# EVGP_Estop_Daugherboard.net
KiCad netlist of a schematic drawn in EAGLE
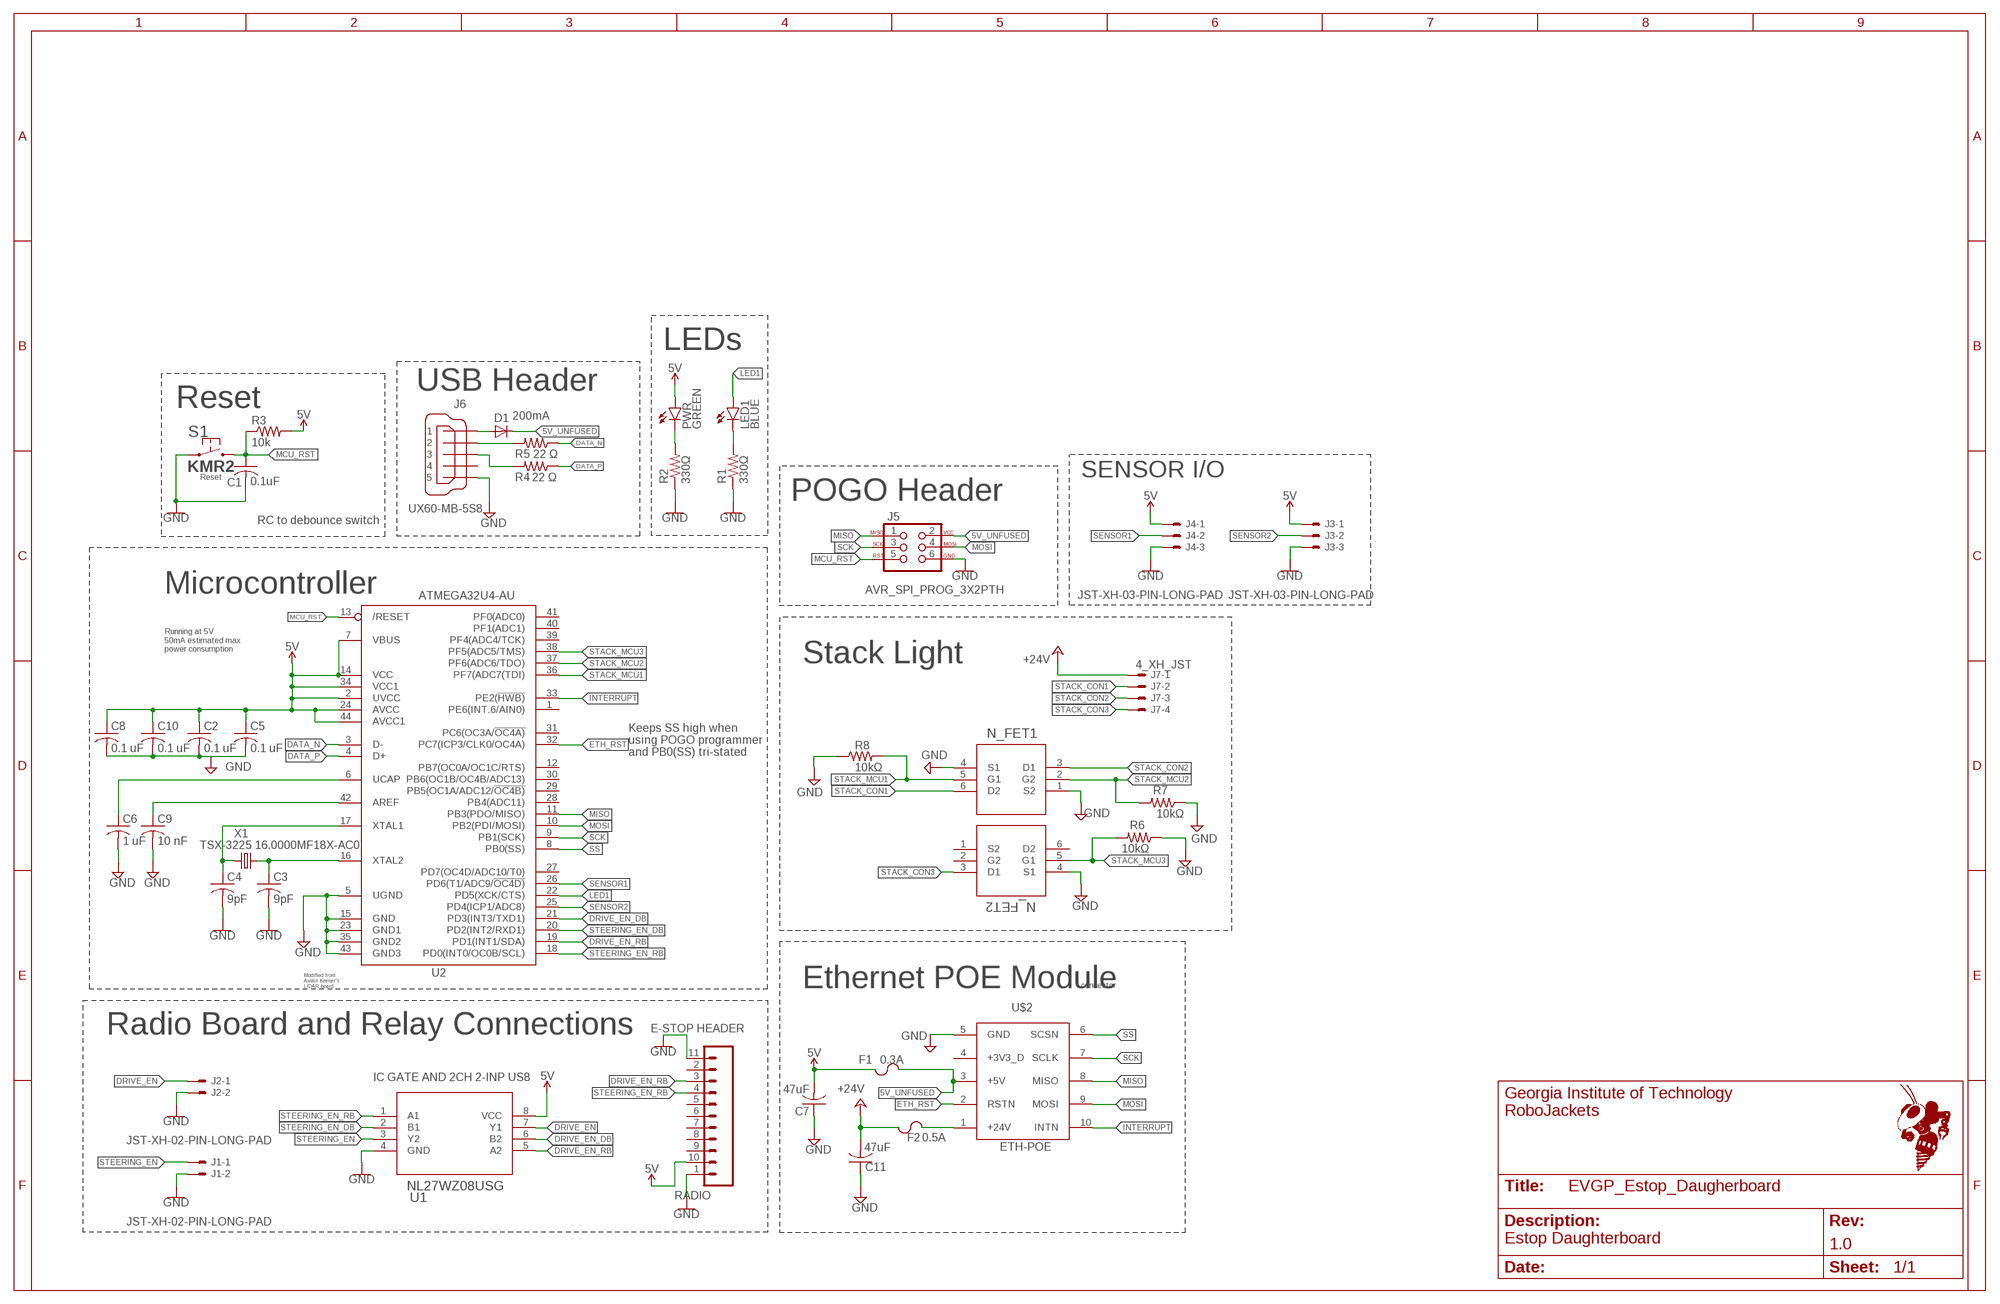
[diagram p0: schematic, sheet 1]

(export (version "E")
  (design (tool "Eeschema 10.0.6"))
  (components
    (comp (ref "C1")
      (value "0.1uF")
      (footprint "eagle-import:C0603")
      (libsource (lib "eagle-import") (part "C-USC0603"))
    )
    (comp (ref "C2")
      (value "0.1 uF")
      (footprint "eagle-import:C0603")
      (libsource (lib "eagle-import") (part "resistor_348_C-USC0603"))
    )
    (comp (ref "C3")
      (value "9pF")
      (footprint "eagle-import:C0603")
      (libsource (lib "eagle-import") (part "resistor_348_C-USC0603"))
    )
    (comp (ref "C4")
      (value "9pF")
      (footprint "eagle-import:C0603")
      (libsource (lib "eagle-import") (part "resistor_348_C-USC0603"))
    )
    (comp (ref "C5")
      (value "0.1 uF")
      (footprint "eagle-import:C0603")
      (libsource (lib "eagle-import") (part "resistor_348_C-USC0603"))
    )
    (comp (ref "C6")
      (value "1 uF")
      (footprint "eagle-import:C0603")
      (libsource (lib "eagle-import") (part "resistor_348_C-USC0603"))
    )
    (comp (ref "C7")
      (value "47uF")
      (footprint "eagle-import:C1206")
      (libsource (lib "eagle-import") (part "C-USC1206"))
    )
    (comp (ref "C8")
      (value "0.1 uF")
      (footprint "eagle-import:C0603")
      (libsource (lib "eagle-import") (part "resistor_348_C-USC0603"))
    )
    (comp (ref "C9")
      (value "10 nF")
      (footprint "eagle-import:C0603")
      (libsource (lib "eagle-import") (part "resistor_348_C-USC0603"))
    )
    (comp (ref "C10")
      (value "0.1 uF")
      (footprint "eagle-import:C0603")
      (libsource (lib "eagle-import") (part "resistor_348_C-USC0603"))
    )
    (comp (ref "C11")
      (value "47uF")
      (footprint "eagle-import:C1206")
      (libsource (lib "eagle-import") (part "C-USC1206"))
    )
    (comp (ref "D1")
      (value "200mA")
      (footprint "eagle-import:SOD323-R")
      (libsource (lib "eagle-import") (part "DIODE-SOD323-R"))
    )
    (comp (ref "F1")
      (value "0.3A")
      (footprint "eagle-import:F1206")
      (libsource (lib "eagle-import") (part "CHIP_FUSE1206"))
    )
    (comp (ref "F2")
      (value "0.5A")
      (footprint "eagle-import:F1206")
      (libsource (lib "eagle-import") (part "CHIP_FUSE1206"))
    )
    (comp (ref "J1")
      (value "JST-XH-02-PIN-LONG-PAD")
      (footprint "eagle-import:JST-XH-02-PACKAGE-LONG-PAD")
      (libsource (lib "eagle-import") (part "JST-XH-02-PIN-LONG-PAD"))
    )
    (comp (ref "J2")
      (value "JST-XH-02-PIN-LONG-PAD")
      (footprint "eagle-import:JST-XH-02-PACKAGE-LONG-PAD")
      (libsource (lib "eagle-import") (part "JST-XH-02-PIN-LONG-PAD"))
    )
    (comp (ref "J3")
      (value "JST-XH-03-PIN-LONG-PAD")
      (footprint "eagle-import:JST-XH-03-PACKAGE-LONG-PAD")
      (libsource (lib "eagle-import") (part "JST-XH-03-PIN-LONG-PAD"))
    )
    (comp (ref "J4")
      (value "JST-XH-03-PIN-LONG-PAD")
      (footprint "eagle-import:JST-XH-03-PACKAGE-LONG-PAD")
      (libsource (lib "eagle-import") (part "JST-XH-03-PIN-LONG-PAD"))
    )
    (comp (ref "J5")
      (value "AVR_SPI_PROG_3X2PTH")
      (footprint "eagle-import:2X3")
      (libsource (lib "eagle-import") (part "AVR_SPI_PROG_3X2PTH"))
    )
    (comp (ref "J6")
      (value "UX60-MB-5S8")
      (footprint "eagle-import:UX60-MB-5S8")
      (libsource (lib "eagle-import") (part "UX60-MB-5S?8"))
    )
    (comp (ref "J7")
      (value "4_XH_JST")
      (footprint "eagle-import:JST-XH-04-PACKAGE-LONG-PAD")
      (libsource (lib "eagle-import") (part "JST-XH-04-PIN-LONG-PAD"))
    )
    (comp (ref "LED1")
      (value "BLUE")
      (footprint "eagle-import:CHIP-LED0603")
      (libsource (lib "eagle-import") (part "LEDCHIP-LED0603"))
    )
    (comp (ref "PWR")
      (value "GREEN")
      (footprint "eagle-import:CHIP-LED0603")
      (libsource (lib "eagle-import") (part "LEDCHIP-LED0603"))
    )
    (comp (ref "Q1")
      (value "N_FET2")
      (footprint "eagle-import:SOT-363")
      (fields (field (name "MANUFACTURER_PART_NUMBER") "BSS84DW7F"))
      (libsource (lib "eagle-import") (part "BSS84DW-7-F"))
    )
    (comp (ref "Q2")
      (value "N_FET1")
      (footprint "eagle-import:SOT-363")
      (fields (field (name "MANUFACTURER_PART_NUMBER") "BSS84DW7F"))
      (libsource (lib "eagle-import") (part "BSS84DW-7-F"))
    )
    (comp (ref "R1")
      (value "330Ω")
      (footprint "eagle-import:R0603")
      (libsource (lib "eagle-import") (part "R-US_R0603"))
    )
    (comp (ref "R2")
      (value "330Ω")
      (footprint "eagle-import:R0603")
      (libsource (lib "eagle-import") (part "R-US_R0603"))
    )
    (comp (ref "R3")
      (value "10k")
      (footprint "eagle-import:R0603")
      (libsource (lib "eagle-import") (part "R-US_R0603"))
    )
    (comp (ref "R4")
      (value "22 Ω")
      (footprint "eagle-import:R0603")
      (libsource (lib "eagle-import") (part "R-US_R0603"))
    )
    (comp (ref "R5")
      (value "22 Ω")
      (footprint "eagle-import:R0603")
      (libsource (lib "eagle-import") (part "R-US_R0603"))
    )
    (comp (ref "R6")
      (value "10kΩ")
      (footprint "eagle-import:R0603")
      (libsource (lib "eagle-import") (part "R-US_R0603"))
    )
    (comp (ref "R7")
      (value "10kΩ")
      (footprint "eagle-import:R0603")
      (libsource (lib "eagle-import") (part "R-US_R0603"))
    )
    (comp (ref "R8")
      (value "10kΩ")
      (footprint "eagle-import:R0603")
      (libsource (lib "eagle-import") (part "R-US_R0603"))
    )
    (comp (ref "RADIO")
      (value "E-STOP HEADER")
      (footprint "eagle-import:RADIO_V1.3")
      (libsource (lib "eagle-import") (part "ESTOP_RADIO"))
    )
    (comp (ref "S1")
      (value "KMR2")
      (footprint "eagle-import:KMR2")
      (fields (field (name "FUNCTION") "Reset"))
      (libsource (lib "eagle-import") (part "KMR2"))
    )
    (comp (ref "U$2")
      (value "ETH-POE")
      (footprint "eagle-import:HDRVR10W64P4000X254_2X5_1016X508X254B")
      (libsource (lib "eagle-import") (part "ETH-POE"))
    )
    (comp (ref "U1")
      (value "NL27WZ08USG")
      (footprint "eagle-import:US8_2P40X2P10")
      (libsource (lib "eagle-import") (part "NL27WZ08USG"))
    )
    (comp (ref "U2")
      (value "ATMEGA32U4-AU")
      (footprint "eagle-import:TQFP44")
      (libsource (lib "eagle-import") (part "ATMEGA32U4-AU"))
    )
    (comp (ref "X1")
      (value "TSX-3225 16.0000MF18X-AC0")
      (footprint "eagle-import:XTAL-3.2X2.5")
      (libsource (lib "eagle-import") (part "XTAL-3.2X2.5"))
    )
  )
  (nets
    (net (code "1") (name "+24V") (class "Default")
      (node (ref "C11") (pin "2") (pinfunction "2_2") (pintype "passive"))
      (node (ref "F2") (pin "1") (pinfunction "1_1") (pintype "bidirectional"))
      (node (ref "J7") (pin "1") (pinfunction "S_1") (pintype "passive"))
    )
    (net (code "2") (name "5V") (class "Default")
      (node (ref "C10") (pin "1") (pinfunction "1_1") (pintype "passive"))
      (node (ref "C2") (pin "1") (pinfunction "1_1") (pintype "passive"))
      (node (ref "C5") (pin "1") (pinfunction "1_1") (pintype "passive"))
      (node (ref "C7") (pin "2") (pinfunction "2_2") (pintype "passive"))
      (node (ref "C8") (pin "1") (pinfunction "1_1") (pintype "passive"))
      (node (ref "F1") (pin "1") (pinfunction "1_1") (pintype "bidirectional"))
      (node (ref "J3") (pin "1") (pinfunction "S_1") (pintype "passive"))
      (node (ref "J4") (pin "1") (pinfunction "S_1") (pintype "passive"))
      (node (ref "PWR") (pin "A") (pinfunction "A_A") (pintype "passive"))
      (node (ref "R3") (pin "2") (pinfunction "2_2") (pintype "passive"))
      (node (ref "RADIO") (pin "10") (pinfunction "5V_10") (pintype "passive"))
      (node (ref "U1") (pin "8") (pinfunction "VCC_8") (pintype "power_in"))
      (node (ref "U2") (pin "14") (pinfunction "VCC_14") (pintype "bidirectional"))
      (node (ref "U2") (pin "2") (pinfunction "UVCC_2") (pintype "bidirectional"))
      (node (ref "U2") (pin "24") (pinfunction "AVCC_24") (pintype "bidirectional"))
      (node (ref "U2") (pin "34") (pinfunction "VCC1_34") (pintype "bidirectional"))
      (node (ref "U2") (pin "44") (pinfunction "AVCC1_44") (pintype "bidirectional"))
      (node (ref "U2") (pin "7") (pinfunction "VBUS_7") (pintype "bidirectional"))
    )
    (net (code "3") (name "5V_UNFUSED") (class "Default")
      (node (ref "D1") (pin "C") (pinfunction "C_C") (pintype "passive"))
      (node (ref "F1") (pin "2") (pinfunction "2_2") (pintype "bidirectional"))
      (node (ref "J5") (pin "2") (pinfunction "2_2") (pintype "passive"))
      (node (ref "U$2") (pin "3") (pinfunction "+5V_3") (pintype "bidirectional"))
    )
    (net (code "4") (name "DATA_N") (class "Default")
      (node (ref "R5") (pin "1") (pinfunction "1_1") (pintype "passive"))
      (node (ref "U2") (pin "3") (pinfunction "D-_3") (pintype "bidirectional"))
    )
    (net (code "5") (name "DATA_P") (class "Default")
      (node (ref "R4") (pin "1") (pinfunction "1_1") (pintype "passive"))
      (node (ref "U2") (pin "4") (pinfunction "D+_4") (pintype "bidirectional"))
    )
    (net (code "6") (name "DRIVE_EN") (class "Default")
      (node (ref "J2") (pin "1") (pinfunction "S_1") (pintype "passive"))
      (node (ref "U1") (pin "7") (pinfunction "Y1_7") (pintype "output"))
    )
    (net (code "7") (name "DRIVE_EN_DB") (class "Default")
      (node (ref "U1") (pin "6") (pinfunction "B2_6") (pintype "input"))
      (node (ref "U2") (pin "21") (pinfunction "PD3(INT3/TXD1)_21") (pintype "bidirectional"))
    )
    (net (code "8") (name "DRIVE_EN_RB") (class "Default")
      (node (ref "RADIO") (pin "3") (pinfunction "D1_3") (pintype "passive"))
      (node (ref "U1") (pin "5") (pinfunction "A2_5") (pintype "input"))
      (node (ref "U2") (pin "19") (pinfunction "PD1(INT1/SDA)_19") (pintype "bidirectional"))
    )
    (net (code "9") (name "ETH_RST") (class "Default")
      (node (ref "U$2") (pin "2") (pinfunction "RSTN_2") (pintype "bidirectional"))
      (node (ref "U2") (pin "32") (pinfunction "PC7(ICP3/CLK0/OC4A)_32") (pintype "bidirectional"))
    )
    (net (code "10") (name "GND") (class "Default")
      (node (ref "C1") (pin "2") (pinfunction "2_2") (pintype "passive"))
      (node (ref "C10") (pin "2") (pinfunction "2_2") (pintype "passive"))
      (node (ref "C11") (pin "1") (pinfunction "1_1") (pintype "passive"))
      (node (ref "C2") (pin "2") (pinfunction "2_2") (pintype "passive"))
      (node (ref "C3") (pin "2") (pinfunction "2_2") (pintype "passive"))
      (node (ref "C4") (pin "2") (pinfunction "2_2") (pintype "passive"))
      (node (ref "C5") (pin "2") (pinfunction "2_2") (pintype "passive"))
      (node (ref "C6") (pin "2") (pinfunction "2_2") (pintype "passive"))
      (node (ref "C7") (pin "1") (pinfunction "1_1") (pintype "passive"))
      (node (ref "C8") (pin "2") (pinfunction "2_2") (pintype "passive"))
      (node (ref "C9") (pin "2") (pinfunction "2_2") (pintype "passive"))
      (node (ref "J1") (pin "2") (pinfunction "S_2") (pintype "passive"))
      (node (ref "J2") (pin "2") (pinfunction "S_2") (pintype "passive"))
      (node (ref "J3") (pin "3") (pinfunction "S_3") (pintype "passive"))
      (node (ref "J4") (pin "3") (pinfunction "S_3") (pintype "passive"))
      (node (ref "J5") (pin "6") (pinfunction "6_6") (pintype "passive"))
      (node (ref "J6") (pin "5") (pinfunction "5_5") (pintype "passive"))
      (node (ref "Q1") (pin "4") (pinfunction "S1_4") (pintype "passive"))
      (node (ref "Q2") (pin "1") (pinfunction "S2_1") (pintype "passive"))
      (node (ref "Q2") (pin "4") (pinfunction "S1_4") (pintype "passive"))
      (node (ref "R1") (pin "1") (pinfunction "1_1") (pintype "passive"))
      (node (ref "R2") (pin "1") (pinfunction "1_1") (pintype "passive"))
      (node (ref "R6") (pin "1") (pinfunction "1_1") (pintype "passive"))
      (node (ref "R7") (pin "1") (pinfunction "1_1") (pintype "passive"))
      (node (ref "R8") (pin "1") (pinfunction "1_1") (pintype "passive"))
      (node (ref "RADIO") (pin "1") (pinfunction "GND_1") (pintype "passive"))
      (node (ref "RADIO") (pin "11") (pinfunction "GND_11") (pintype "passive"))
      (node (ref "S1") (pin "1.1") (pinfunction "1_1.1") (pintype "passive"))
      (node (ref "S1") (pin "1.2") (pinfunction "1_1.2") (pintype "passive"))
      (node (ref "U$2") (pin "5") (pinfunction "GND_5") (pintype "bidirectional"))
      (node (ref "U1") (pin "4") (pinfunction "GND_4") (pintype "power_in"))
      (node (ref "U2") (pin "15") (pinfunction "GND_15") (pintype "bidirectional"))
      (node (ref "U2") (pin "23") (pinfunction "GND1_23") (pintype "bidirectional"))
      (node (ref "U2") (pin "35") (pinfunction "GND2_35") (pintype "bidirectional"))
      (node (ref "U2") (pin "43") (pinfunction "GND3_43") (pintype "bidirectional"))
      (node (ref "U2") (pin "5") (pinfunction "UGND_5") (pintype "bidirectional"))
    )
    (net (code "11") (name "INTERRUPT") (class "Default")
      (node (ref "U$2") (pin "10") (pinfunction "INTN_10") (pintype "bidirectional"))
      (node (ref "U2") (pin "33") (pinfunction "PE2(~{HWB})_33") (pintype "bidirectional"))
    )
    (net (code "12") (name "LED1") (class "Default")
      (node (ref "LED1") (pin "A") (pinfunction "A_A") (pintype "passive"))
      (node (ref "U2") (pin "22") (pinfunction "PD5(XCK/CTS)_22") (pintype "bidirectional"))
    )
    (net (code "13") (name "MCU_RST") (class "Default")
      (node (ref "C1") (pin "1") (pinfunction "1_1") (pintype "passive"))
      (node (ref "J5") (pin "5") (pinfunction "5_5") (pintype "passive"))
      (node (ref "R3") (pin "1") (pinfunction "1_1") (pintype "passive"))
      (node (ref "S1") (pin "2.1") (pinfunction "2_2.1") (pintype "passive"))
      (node (ref "S1") (pin "2.2") (pinfunction "2_2.2") (pintype "passive"))
      (node (ref "U2") (pin "13") (pinfunction "/RESET_13") (pintype "bidirectional"))
    )
    (net (code "14") (name "MISO") (class "Default")
      (node (ref "J5") (pin "1") (pinfunction "1_1") (pintype "passive"))
      (node (ref "U$2") (pin "8") (pinfunction "MISO_8") (pintype "bidirectional"))
      (node (ref "U2") (pin "11") (pinfunction "PB3(PDO/MISO)_11") (pintype "bidirectional"))
    )
    (net (code "15") (name "MOSI") (class "Default")
      (node (ref "J5") (pin "4") (pinfunction "4_4") (pintype "passive"))
      (node (ref "U$2") (pin "9") (pinfunction "MOSI_9") (pintype "bidirectional"))
      (node (ref "U2") (pin "10") (pinfunction "PB2(PDI/MOSI)_10") (pintype "bidirectional"))
    )
    (net (code "16") (name "Net-(D1-PadA)") (class "Default")
      (node (ref "D1") (pin "A") (pinfunction "A_A") (pintype "passive"))
      (node (ref "J6") (pin "1") (pinfunction "1_1") (pintype "passive"))
    )
    (net (code "17") (name "Net-(J6-Pad2)") (class "Default")
      (node (ref "J6") (pin "2") (pinfunction "2_2") (pintype "passive"))
      (node (ref "R5") (pin "2") (pinfunction "2_2") (pintype "passive"))
    )
    (net (code "18") (name "Net-(J6-Pad3)") (class "Default")
      (node (ref "J6") (pin "3") (pinfunction "3_3") (pintype "passive"))
      (node (ref "R4") (pin "2") (pinfunction "2_2") (pintype "passive"))
    )
    (net (code "19") (name "Net-(LED1-PadC)") (class "Default")
      (node (ref "LED1") (pin "C") (pinfunction "C_C") (pintype "passive"))
      (node (ref "R1") (pin "2") (pinfunction "2_2") (pintype "passive"))
    )
    (net (code "20") (name "Net-(PWR-PadC)") (class "Default")
      (node (ref "PWR") (pin "C") (pinfunction "C_C") (pintype "passive"))
      (node (ref "R2") (pin "2") (pinfunction "2_2") (pintype "passive"))
    )
    (net (code "21") (name "Net-(U$2-+24V)") (class "Default")
      (node (ref "F2") (pin "2") (pinfunction "2_2") (pintype "bidirectional"))
      (node (ref "U$2") (pin "1") (pinfunction "+24V_1") (pintype "bidirectional"))
    )
    (net (code "22") (name "Net-(U2-AREF)") (class "Default")
      (node (ref "C9") (pin "1") (pinfunction "1_1") (pintype "passive"))
      (node (ref "U2") (pin "42") (pinfunction "AREF_42") (pintype "bidirectional"))
    )
    (net (code "23") (name "Net-(U2-UCAP)") (class "Default")
      (node (ref "C6") (pin "1") (pinfunction "1_1") (pintype "passive"))
      (node (ref "U2") (pin "6") (pinfunction "UCAP_6") (pintype "bidirectional"))
    )
    (net (code "24") (name "Net-(U2-XTAL1)") (class "Default")
      (node (ref "C4") (pin "1") (pinfunction "1_1") (pintype "passive"))
      (node (ref "U2") (pin "17") (pinfunction "XTAL1_17") (pintype "bidirectional"))
      (node (ref "X1") (pin "1") (pinfunction "1_1") (pintype "passive"))
    )
    (net (code "25") (name "Net-(U2-XTAL2)") (class "Default")
      (node (ref "C3") (pin "1") (pinfunction "1_1") (pintype "passive"))
      (node (ref "U2") (pin "16") (pinfunction "XTAL2_16") (pintype "bidirectional"))
      (node (ref "X1") (pin "3") (pinfunction "2_3") (pintype "passive"))
    )
    (net (code "26") (name "SCK") (class "Default")
      (node (ref "J5") (pin "3") (pinfunction "3_3") (pintype "passive"))
      (node (ref "U$2") (pin "7") (pinfunction "SCLK_7") (pintype "bidirectional"))
      (node (ref "U2") (pin "9") (pinfunction "PB1(SCK)_9") (pintype "bidirectional"))
    )
    (net (code "27") (name "SENSOR1") (class "Default")
      (node (ref "J4") (pin "2") (pinfunction "S_2") (pintype "passive"))
      (node (ref "U2") (pin "26") (pinfunction "PD6(T1/ADC9/~{OC4D})_26") (pintype "bidirectional"))
    )
    (net (code "28") (name "SENSOR2") (class "Default")
      (node (ref "J3") (pin "2") (pinfunction "S_2") (pintype "passive"))
      (node (ref "U2") (pin "25") (pinfunction "PD4(ICP1/ADC8)_25") (pintype "bidirectional"))
    )
    (net (code "29") (name "SS") (class "Default")
      (node (ref "U$2") (pin "6") (pinfunction "SCSN_6") (pintype "bidirectional"))
      (node (ref "U2") (pin "8") (pinfunction "PB0(SS)_8") (pintype "bidirectional"))
    )
    (net (code "30") (name "STACK_CON1") (class "Default")
      (node (ref "J7") (pin "2") (pinfunction "S_2") (pintype "passive"))
      (node (ref "Q2") (pin "6") (pinfunction "D2_6") (pintype "passive"))
    )
    (net (code "31") (name "STACK_CON2") (class "Default")
      (node (ref "J7") (pin "3") (pinfunction "S_3") (pintype "passive"))
      (node (ref "Q2") (pin "3") (pinfunction "D1_3") (pintype "passive"))
    )
    (net (code "32") (name "STACK_CON3") (class "Default")
      (node (ref "J7") (pin "4") (pinfunction "S_4") (pintype "passive"))
      (node (ref "Q1") (pin "3") (pinfunction "D1_3") (pintype "passive"))
    )
    (net (code "33") (name "STACK_MCU1") (class "Default")
      (node (ref "Q2") (pin "5") (pinfunction "G1_5") (pintype "passive"))
      (node (ref "R8") (pin "2") (pinfunction "2_2") (pintype "passive"))
      (node (ref "U2") (pin "36") (pinfunction "PF7(ADC7(TDI)_36") (pintype "bidirectional"))
    )
    (net (code "34") (name "STACK_MCU2") (class "Default")
      (node (ref "Q2") (pin "2") (pinfunction "G2_2") (pintype "passive"))
      (node (ref "R7") (pin "2") (pinfunction "2_2") (pintype "passive"))
      (node (ref "U2") (pin "37") (pinfunction "PF6(ADC6/TDO)_37") (pintype "bidirectional"))
    )
    (net (code "35") (name "STACK_MCU3") (class "Default")
      (node (ref "Q1") (pin "5") (pinfunction "G1_5") (pintype "passive"))
      (node (ref "R6") (pin "2") (pinfunction "2_2") (pintype "passive"))
      (node (ref "U2") (pin "38") (pinfunction "PF5(ADC5/TMS)_38") (pintype "bidirectional"))
    )
    (net (code "36") (name "STEERING_EN") (class "Default")
      (node (ref "J1") (pin "1") (pinfunction "S_1") (pintype "passive"))
      (node (ref "U1") (pin "3") (pinfunction "Y2_3") (pintype "output"))
    )
    (net (code "37") (name "STEERING_EN_DB") (class "Default")
      (node (ref "U1") (pin "2") (pinfunction "B1_2") (pintype "input"))
      (node (ref "U2") (pin "20") (pinfunction "PD2(INT2/RXD1)_20") (pintype "bidirectional"))
    )
    (net (code "38") (name "STEERING_EN_RB") (class "Default")
      (node (ref "RADIO") (pin "4") (pinfunction "D2_4") (pintype "passive"))
      (node (ref "U1") (pin "1") (pinfunction "A1_1") (pintype "input"))
      (node (ref "U2") (pin "18") (pinfunction "PD0(INT0/OC0B/SCL)_18") (pintype "bidirectional"))
    )
    (net (code "39") (name "unconnected-(J6-Pad4)") (class "Default")
      (node (ref "J6") (pin "4") (pinfunction "4_4") (pintype "passive"))
    )
    (net (code "40") (name "unconnected-(Q1-D2-Pad6)") (class "Default")
      (node (ref "Q1") (pin "6") (pinfunction "D2_6") (pintype "passive"))
    )
    (net (code "41") (name "unconnected-(Q1-G2-Pad2)") (class "Default")
      (node (ref "Q1") (pin "2") (pinfunction "G2_2") (pintype "passive"))
    )
    (net (code "42") (name "unconnected-(Q1-S2-Pad1)") (class "Default")
      (node (ref "Q1") (pin "1") (pinfunction "S2_1") (pintype "passive"))
    )
    (net (code "43") (name "unconnected-(RADIO-D3-Pad5)") (class "Default")
      (node (ref "RADIO") (pin "5") (pinfunction "D3_5") (pintype "passive"))
    )
    (net (code "44") (name "unconnected-(RADIO-D4-Pad6)") (class "Default")
      (node (ref "RADIO") (pin "6") (pinfunction "D4_6") (pintype "passive"))
    )
    (net (code "45") (name "unconnected-(RADIO-D5-Pad7)") (class "Default")
      (node (ref "RADIO") (pin "7") (pinfunction "D5_7") (pintype "passive"))
    )
    (net (code "46") (name "unconnected-(RADIO-D6-Pad8)") (class "Default")
      (node (ref "RADIO") (pin "8") (pinfunction "D6_8") (pintype "passive"))
    )
    (net (code "47") (name "unconnected-(RADIO-D7-Pad9)") (class "Default")
      (node (ref "RADIO") (pin "9") (pinfunction "D7_9") (pintype "passive"))
    )
    (net (code "48") (name "unconnected-(RADIO-RST-Pad2)") (class "Default")
      (node (ref "RADIO") (pin "2") (pinfunction "RST_2") (pintype "passive"))
    )
    (net (code "49") (name "unconnected-(U$2-+3V3_D-Pad4)") (class "Default")
      (node (ref "U$2") (pin "4") (pinfunction "+3V3_D_4") (pintype "bidirectional"))
    )
    (net (code "50") (name "unconnected-(U2-PB4(ADC11)-Pad28)") (class "Default")
      (node (ref "U2") (pin "28") (pinfunction "PB4(ADC11)_28") (pintype "bidirectional"))
    )
    (net (code "51") (name "unconnected-(U2-PB5(OC1A{slash}ADC12{slash}~{OC4B})-Pad29)") (class "Default")
      (node (ref "U2") (pin "29") (pinfunction "PB5(OC1A/ADC12/~{OC4B})_29") (pintype "bidirectional"))
    )
    (net (code "52") (name "unconnected-(U2-PB6(OC1B{slash}OC4B{slash}ADC13)-Pad30)") (class "Default")
      (node (ref "U2") (pin "30") (pinfunction "PB6(OC1B/OC4B/ADC13)_30") (pintype "bidirectional"))
    )
    (net (code "53") (name "unconnected-(U2-PB7(OC0A{slash}OC1C{slash}RTS)-Pad12)") (class "Default")
      (node (ref "U2") (pin "12") (pinfunction "PB7(OC0A/OC1C/RTS)_12") (pintype "bidirectional"))
    )
    (net (code "54") (name "unconnected-(U2-PC6(OC3A{slash}~{OC4A})-Pad31)") (class "Default")
      (node (ref "U2") (pin "31") (pinfunction "PC6(OC3A/~{OC4A})_31") (pintype "bidirectional"))
    )
    (net (code "55") (name "unconnected-(U2-PD7(OC4D{slash}ADC10{slash}T0)-Pad27)") (class "Default")
      (node (ref "U2") (pin "27") (pinfunction "PD7(OC4D/ADC10/T0)_27") (pintype "bidirectional"))
    )
    (net (code "56") (name "unconnected-(U2-PE6(INT.6{slash}AIN0)-Pad1)") (class "Default")
      (node (ref "U2") (pin "1") (pinfunction "PE6(INT.6/AIN0)_1") (pintype "bidirectional"))
    )
    (net (code "57") (name "unconnected-(U2-PF0(ADC0)-Pad41)") (class "Default")
      (node (ref "U2") (pin "41") (pinfunction "PF0(ADC0)_41") (pintype "bidirectional"))
    )
    (net (code "58") (name "unconnected-(U2-PF1(ADC1)-Pad40)") (class "Default")
      (node (ref "U2") (pin "40") (pinfunction "PF1(ADC1)_40") (pintype "bidirectional"))
    )
    (net (code "59") (name "unconnected-(U2-PF4(ADC4{slash}TCK)-Pad39)") (class "Default")
      (node (ref "U2") (pin "39") (pinfunction "PF4(ADC4/TCK)_39") (pintype "bidirectional"))
    )
  )
)
